# ESP32SchematicPG2_1.net
KiCad netlist of a schematic drawn in Altium Designer
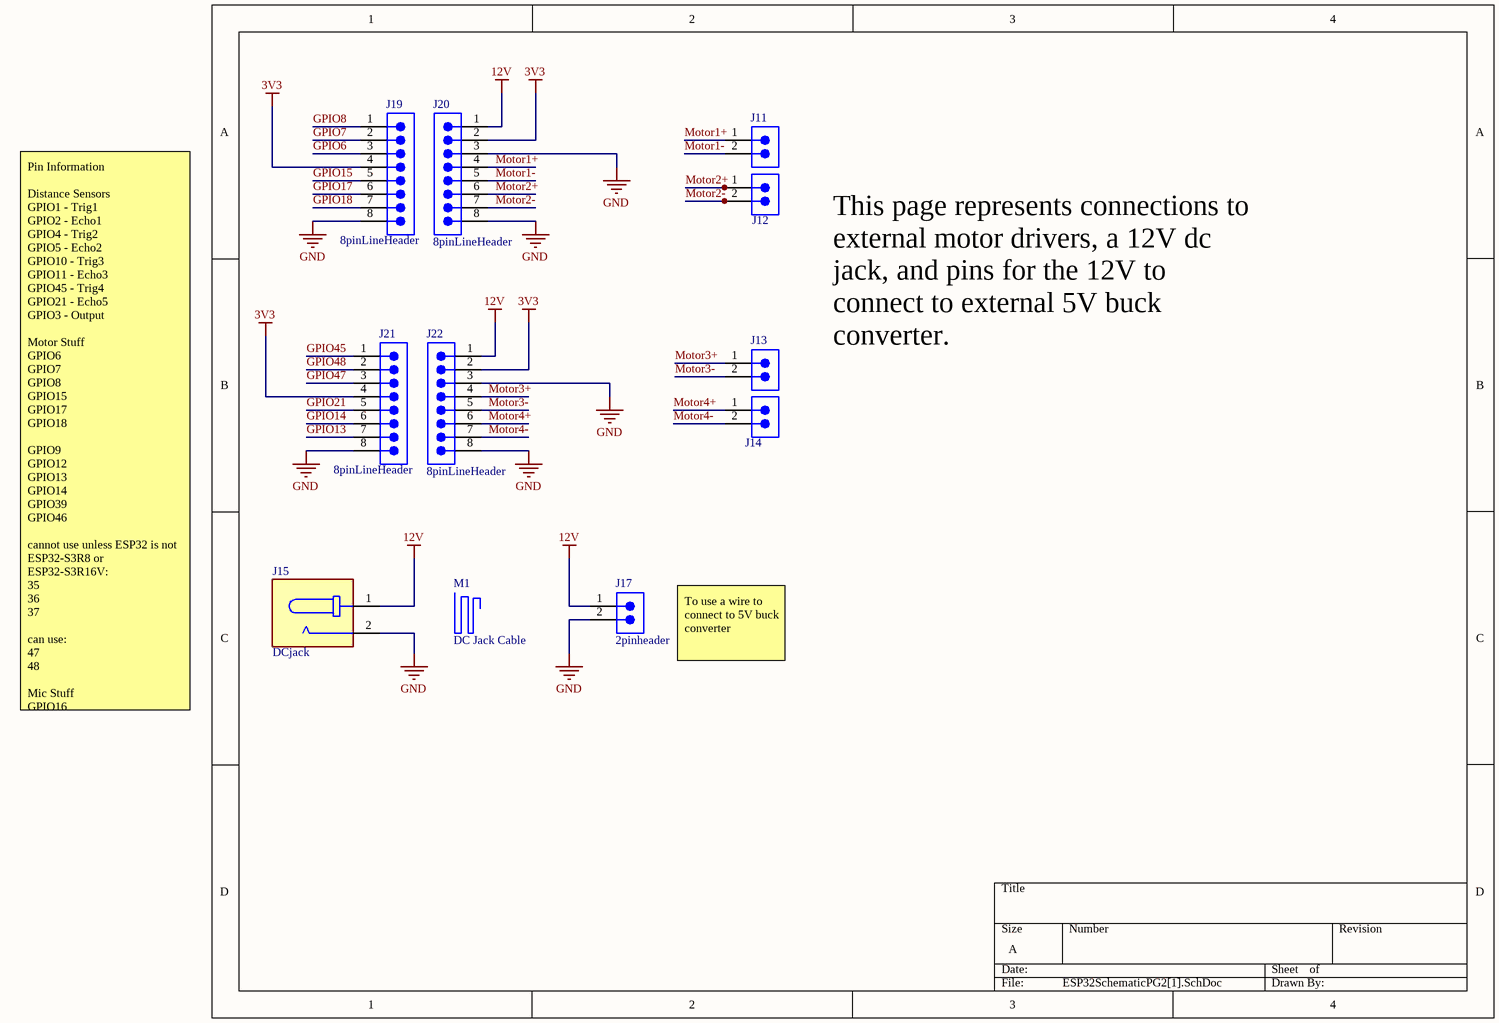
[diagram p0: ESP32SchematicPG2[1].SchDoc]

(export (version "E")
  (design (tool "Eeschema 10.0.6"))
  (components
    (comp (ref "J11")
      (value "2pinheader")
      (footprint "61300211121")
      (description "WR-PHD Straight Male, PCB Header, Through Hole, 1 Rows, 2 Contacts, 2.54mm Pitch")
      (fields
        (field (name "MANUFACTURER") "Wurth Elektronik")
        (field (name "MANUFACTURER PART NUMBER") "61300211121")
      )
      (libsource (lib "Schlib") (part "61300211121"))
    )
    (comp (ref "J12")
      (value "2pinheader")
      (footprint "61300211121")
      (description "WR-PHD Straight Male, PCB Header, Through Hole, 1 Rows, 2 Contacts, 2.54mm Pitch")
      (fields
        (field (name "MANUFACTURER") "Wurth Elektronik")
        (field (name "MANUFACTURER PART NUMBER") "61300211121")
      )
      (libsource (lib "Schlib") (part "61300211121"))
    )
    (comp (ref "J13")
      (value "2pinheader")
      (footprint "61300211121")
      (description "WR-PHD Straight Male, PCB Header, Through Hole, 1 Rows, 2 Contacts, 2.54mm Pitch")
      (fields
        (field (name "MANUFACTURER") "Wurth Elektronik")
        (field (name "MANUFACTURER PART NUMBER") "61300211121")
      )
      (libsource (lib "Schlib") (part "61300211121"))
    )
    (comp (ref "J14")
      (value "2pinheader")
      (footprint "61300211121")
      (description "WR-PHD Straight Male, PCB Header, Through Hole, 1 Rows, 2 Contacts, 2.54mm Pitch")
      (fields
        (field (name "MANUFACTURER") "Wurth Elektronik")
        (field (name "MANUFACTURER PART NUMBER") "61300211121")
      )
      (libsource (lib "Schlib") (part "61300211121"))
    )
    (comp (ref "J15")
      (value "DCjack")
      (footprint "CUI_PJ-037B")
      (description "2.5 x 6.5 mm, 2.5 A, Horizontal, Through Hole, Dc Power Jack Connector")
      (fields (field (name "MANUFACTURER") "Same Sky") (field (name "MANUFACTURER PART NUMBER") "PJ-037B"))
      (libsource (lib "Schlib") (part "PJ-037B"))
    )
    (comp (ref "J17")
      (value "2pinheader")
      (footprint "61300211121")
      (description "WR-PHD Straight Male, PCB Header, Through Hole, 1 Rows, 2 Contacts, 2.54mm Pitch")
      (fields
        (field (name "MANUFACTURER") "Wurth Elektronik")
        (field (name "MANUFACTURER PART NUMBER") "61300211121")
      )
      (libsource (lib "Schlib") (part "61300211121"))
    )
    (comp (ref "J19")
      (value "8pinLineHeader")
      (footprint "PPTC081LFBN-RC")
      (description "Female, 8C, Straight, .100\"CC; 3.20mm Tail, No Mt. 100u\" Tin; PBT, Phos Bronze, 105 C")
      (fields
        (field (name "MANUFACTURER") "Sullins")
        (field (name "MANUFACTURER PART NUMBER") "PPTC081LFBN-RC")
      )
      (libsource (lib "Schlib") (part "PPTC081LFBN-RC"))
    )
    (comp (ref "J20")
      (value "8pinLineHeader")
      (footprint "PPTC081LFBN-RC")
      (description "Female, 8C, Straight, .100\"CC; 3.20mm Tail, No Mt. 100u\" Tin; PBT, Phos Bronze, 105 C")
      (fields
        (field (name "MANUFACTURER") "Sullins")
        (field (name "MANUFACTURER PART NUMBER") "PPTC081LFBN-RC")
      )
      (libsource (lib "Schlib") (part "PPTC081LFBN-RC"))
    )
    (comp (ref "J21")
      (value "8pinLineHeader")
      (footprint "PPTC081LFBN-RC")
      (description "Female, 8C, Straight, .100\"CC; 3.20mm Tail, No Mt. 100u\" Tin; PBT, Phos Bronze, 105 C")
      (fields
        (field (name "MANUFACTURER") "Sullins")
        (field (name "MANUFACTURER PART NUMBER") "PPTC081LFBN-RC")
      )
      (libsource (lib "Schlib") (part "PPTC081LFBN-RC"))
    )
    (comp (ref "J22")
      (value "8pinLineHeader")
      (footprint "PPTC081LFBN-RC")
      (description "Female, 8C, Straight, .100\"CC; 3.20mm Tail, No Mt. 100u\" Tin; PBT, Phos Bronze, 105 C")
      (fields
        (field (name "MANUFACTURER") "Sullins")
        (field (name "MANUFACTURER PART NUMBER") "PPTC081LFBN-RC")
      )
      (libsource (lib "Schlib") (part "PPTC081LFBN-RC"))
    )
    (comp (ref "M1")
      (value "DC Jack Cable")
      (description "Dc Pwr Cord, 2.5Mm Pl-Free End, 0.5M/Blk Rohs Compliant: Yes ¦Cliff Electronic Components FC592505")
      (fields (field (name "MANUFACTURER") "Cliff") (field (name "MANUFACTURER PART NUMBER") "FC592505"))
      (libsource (lib "Schlib") (part "FC592505"))
    )
  )
  (nets
    (net (code "1") (name "/GPIO6") (class "Default")
      (node (ref "J19") (pin "3") (pinfunction "3_3") (pintype "passive"))
    )
    (net (code "2") (name "/GPIO7") (class "Default")
      (node (ref "J19") (pin "2") (pinfunction "2_2") (pintype "passive"))
    )
    (net (code "3") (name "/GPIO8") (class "Default")
      (node (ref "J19") (pin "1") (pinfunction "1_1") (pintype "passive"))
    )
    (net (code "4") (name "/GPIO13") (class "Default")
      (node (ref "J21") (pin "7") (pinfunction "7_7") (pintype "passive"))
    )
    (net (code "5") (name "/GPIO14") (class "Default")
      (node (ref "J21") (pin "6") (pinfunction "6_6") (pintype "passive"))
    )
    (net (code "6") (name "/GPIO15") (class "Default")
      (node (ref "J19") (pin "5") (pinfunction "5_5") (pintype "passive"))
    )
    (net (code "7") (name "/GPIO17") (class "Default")
      (node (ref "J19") (pin "6") (pinfunction "6_6") (pintype "passive"))
    )
    (net (code "8") (name "/GPIO18") (class "Default")
      (node (ref "J19") (pin "7") (pinfunction "7_7") (pintype "passive"))
    )
    (net (code "9") (name "/GPIO21") (class "Default")
      (node (ref "J21") (pin "5") (pinfunction "5_5") (pintype "passive"))
    )
    (net (code "10") (name "/GPIO45") (class "Default")
      (node (ref "J21") (pin "1") (pinfunction "1_1") (pintype "passive"))
    )
    (net (code "11") (name "/GPIO47") (class "Default")
      (node (ref "J21") (pin "3") (pinfunction "3_3") (pintype "passive"))
    )
    (net (code "12") (name "/GPIO48") (class "Default")
      (node (ref "J21") (pin "2") (pinfunction "2_2") (pintype "passive"))
    )
    (net (code "13") (name "/Motor1+") (class "Default")
      (node (ref "J11") (pin "1") (pinfunction "1_1") (pintype "passive"))
      (node (ref "J20") (pin "4") (pinfunction "4_4") (pintype "passive"))
    )
    (net (code "14") (name "/Motor1-") (class "Default")
      (node (ref "J11") (pin "2") (pinfunction "2_2") (pintype "passive"))
      (node (ref "J20") (pin "5") (pinfunction "5_5") (pintype "passive"))
    )
    (net (code "15") (name "/Motor2+") (class "Default")
      (node (ref "J12") (pin "1") (pinfunction "1_1") (pintype "passive"))
      (node (ref "J20") (pin "6") (pinfunction "6_6") (pintype "passive"))
    )
    (net (code "16") (name "/Motor2-") (class "Default")
      (node (ref "J12") (pin "2") (pinfunction "2_2") (pintype "passive"))
      (node (ref "J20") (pin "7") (pinfunction "7_7") (pintype "passive"))
    )
    (net (code "17") (name "/Motor3+") (class "Default")
      (node (ref "J13") (pin "1") (pinfunction "1_1") (pintype "passive"))
      (node (ref "J22") (pin "4") (pinfunction "4_4") (pintype "passive"))
    )
    (net (code "18") (name "/Motor3-") (class "Default")
      (node (ref "J13") (pin "2") (pinfunction "2_2") (pintype "passive"))
      (node (ref "J22") (pin "5") (pinfunction "5_5") (pintype "passive"))
    )
    (net (code "19") (name "/Motor4+") (class "Default")
      (node (ref "J14") (pin "1") (pinfunction "1_1") (pintype "passive"))
      (node (ref "J22") (pin "6") (pinfunction "6_6") (pintype "passive"))
    )
    (net (code "20") (name "/Motor4-") (class "Default")
      (node (ref "J14") (pin "2") (pinfunction "2_2") (pintype "passive"))
      (node (ref "J22") (pin "7") (pinfunction "7_7") (pintype "passive"))
    )
    (net (code "21") (name "3V3") (class "Default")
      (node (ref "J19") (pin "4") (pinfunction "4_4") (pintype "passive"))
      (node (ref "J20") (pin "2") (pinfunction "2_2") (pintype "passive"))
      (node (ref "J21") (pin "4") (pinfunction "4_4") (pintype "passive"))
      (node (ref "J22") (pin "2") (pinfunction "2_2") (pintype "passive"))
    )
    (net (code "22") (name "12V") (class "Default")
      (node (ref "J15") (pin "1") (pinfunction "1_1") (pintype "passive"))
      (node (ref "J17") (pin "1") (pinfunction "1_1") (pintype "passive"))
      (node (ref "J20") (pin "1") (pinfunction "1_1") (pintype "passive"))
      (node (ref "J22") (pin "1") (pinfunction "1_1") (pintype "passive"))
    )
    (net (code "23") (name "GND") (class "Default")
      (node (ref "J15") (pin "2") (pinfunction "2_2") (pintype "passive"))
      (node (ref "J17") (pin "2") (pinfunction "2_2") (pintype "passive"))
      (node (ref "J19") (pin "8") (pinfunction "8_8") (pintype "passive"))
      (node (ref "J20") (pin "3") (pinfunction "3_3") (pintype "passive"))
      (node (ref "J20") (pin "8") (pinfunction "8_8") (pintype "passive"))
      (node (ref "J21") (pin "8") (pinfunction "8_8") (pintype "passive"))
      (node (ref "J22") (pin "3") (pinfunction "3_3") (pintype "passive"))
      (node (ref "J22") (pin "8") (pinfunction "8_8") (pintype "passive"))
    )
  )
)
